# SICRO-Main_v2.net
KiCad netlist of a schematic drawn in EasyEDA Pro
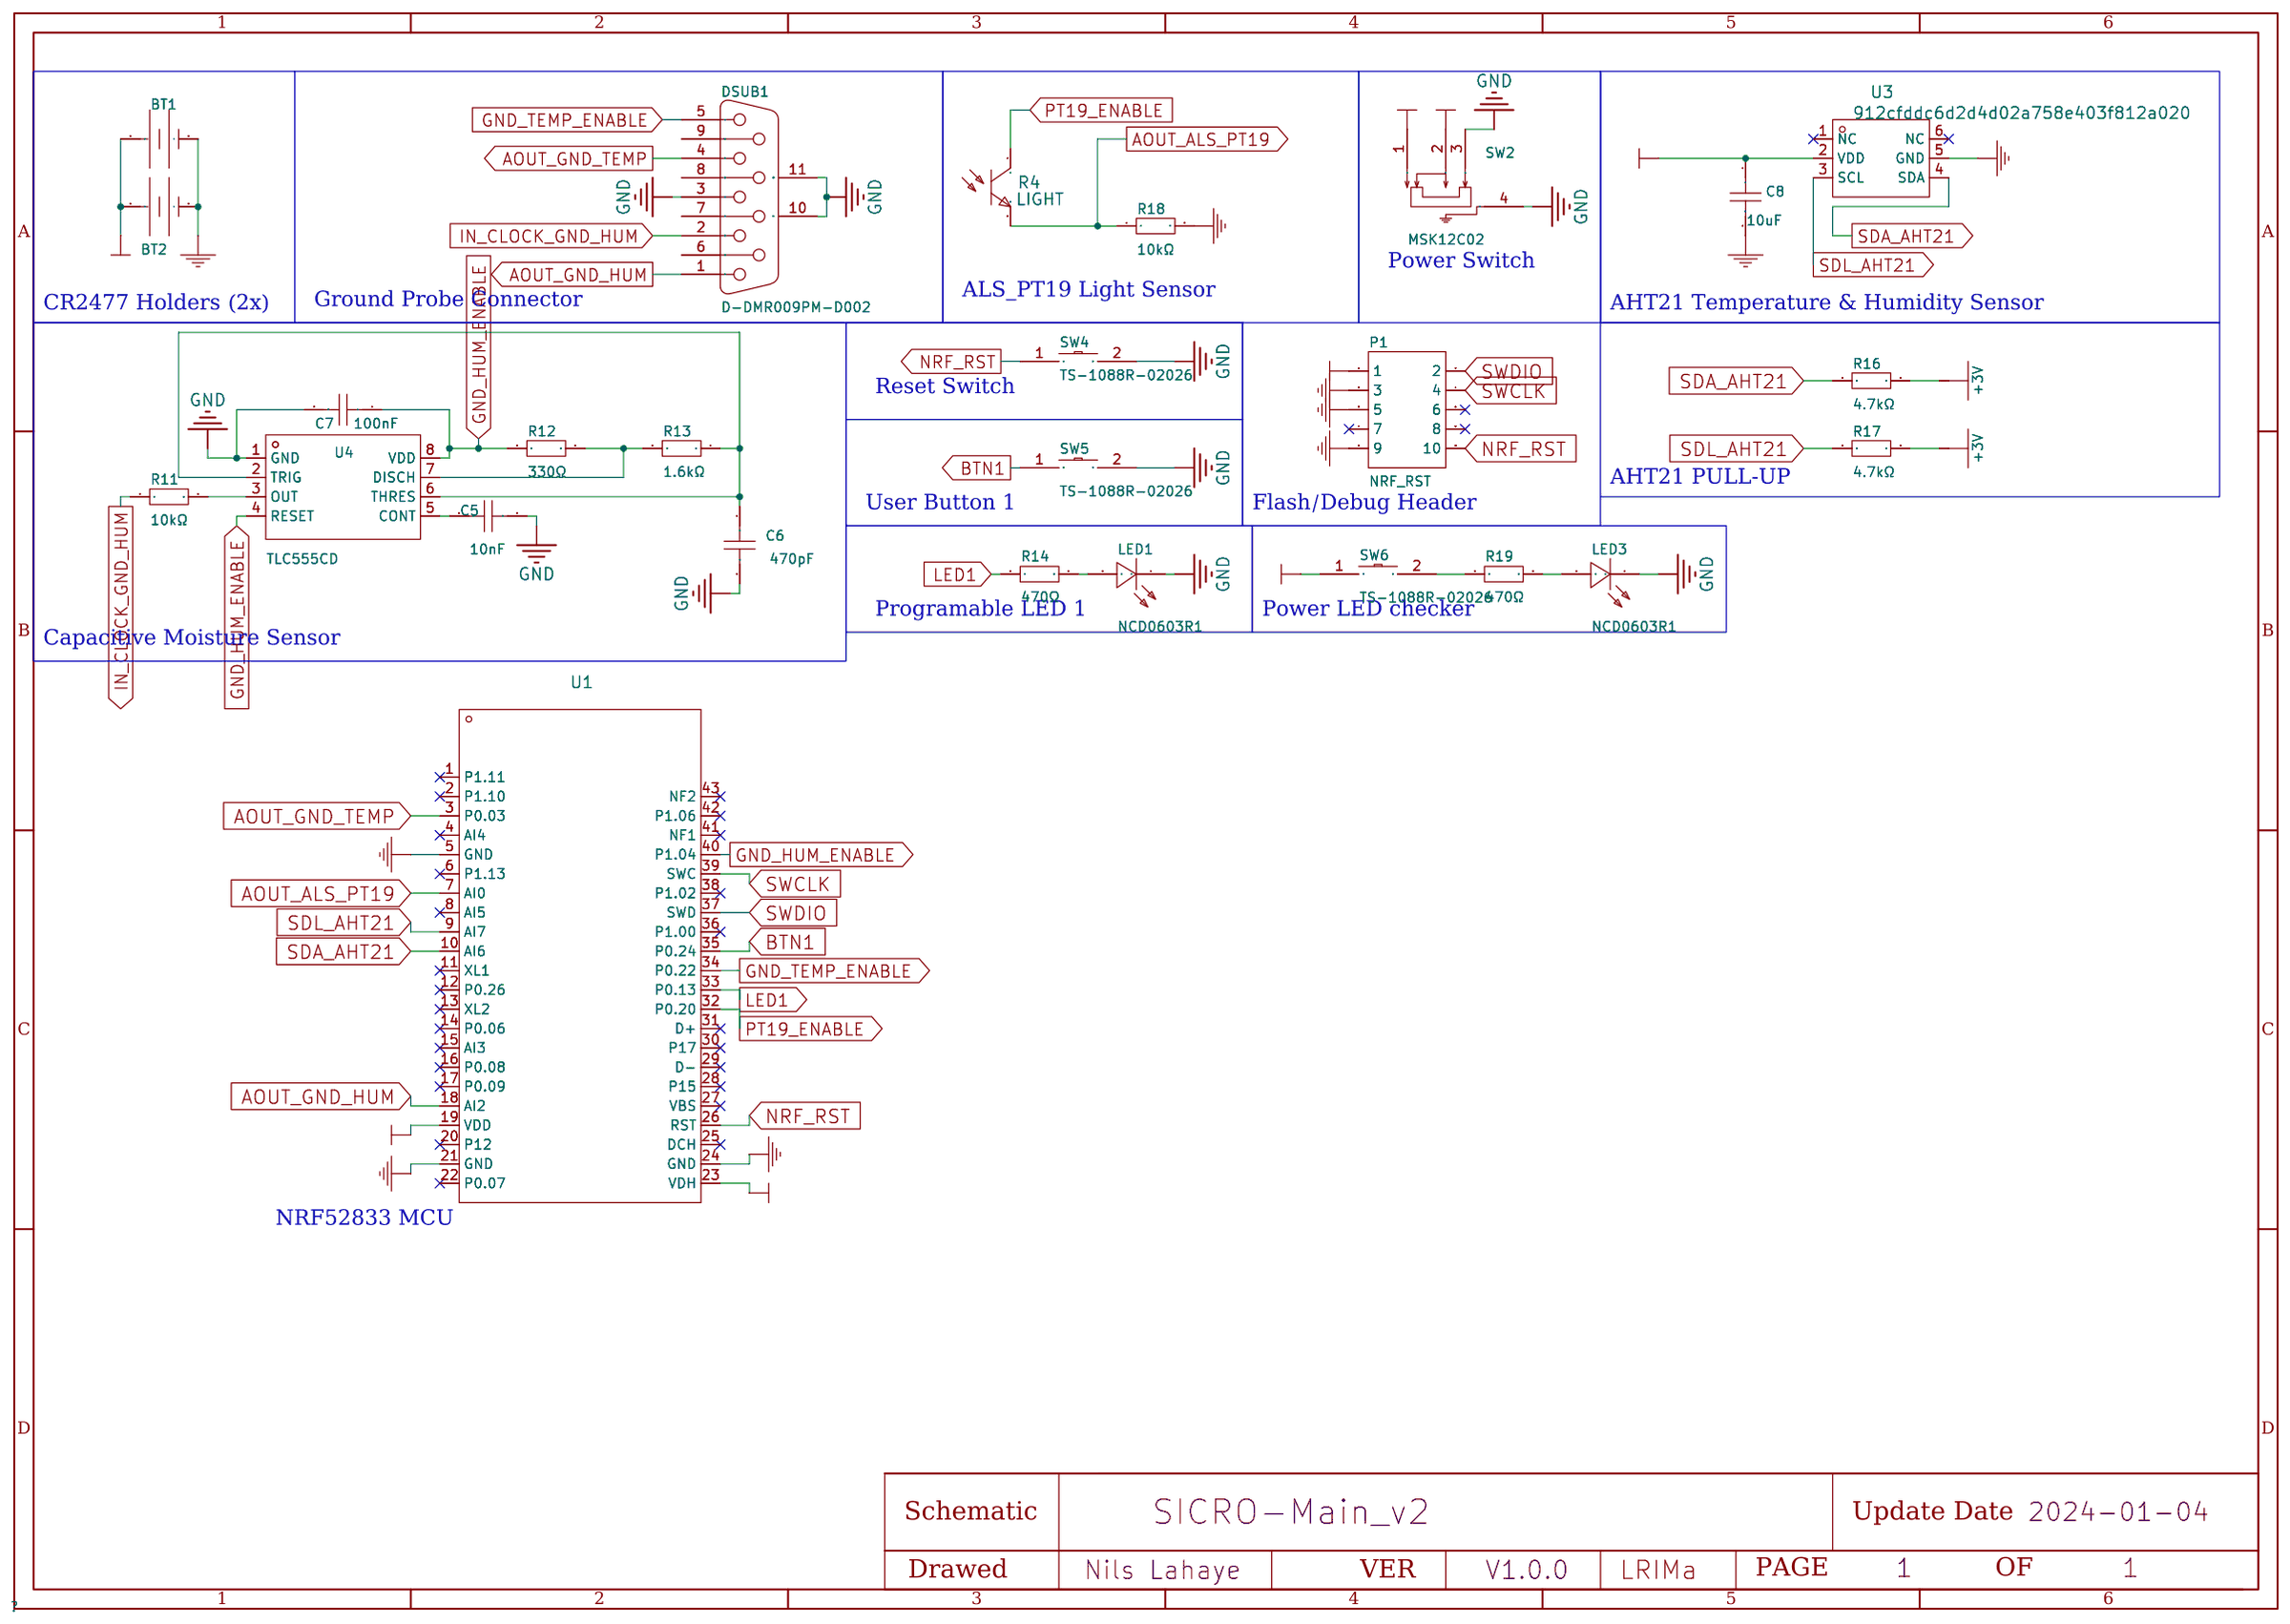
[diagram p0: schematic sheet]

(export (version "E")
  (design (tool "Eeschema 10.0.6"))
  (components
    (comp (ref "BT1")
      (value "BS-24-A1AJ008")
      (footprint "easyedapro:BAT-TH_BS-24-A1AJ013")
      (fields (field (name "Manufacturer") "MYOUNG(美阳)"))
      (libsource (lib "easyedapro") (part "BS-24-A1AJ008"))
    )
    (comp (ref "BT2")
      (value "BS-24-A1AJ008")
      (footprint "easyedapro:BAT-TH_BS-24-A1AJ013")
      (fields (field (name "Manufacturer") "MYOUNG(美阳)"))
      (libsource (lib "easyedapro") (part "BS-24-A1AJ008"))
    )
    (comp (ref "C5")
      (value "10nF")
      (fields
        (field (name "Manufacturer Part") "CC0603KRX7R9BB103")
        (field (name "Manufacturer") "YAGEO(国巨)")
        (field (name "Tolerance") "±10%")
      )
      (libsource (lib "easyedapro") (part "CAP"))
    )
    (comp (ref "C6")
      (value "470pF")
      (fields
        (field (name "Manufacturer Part") "0603B471K500NT")
        (field (name "Manufacturer") "FH(风华)")
        (field (name "Tolerance") "±10%")
      )
      (libsource (lib "easyedapro") (part "CAP"))
    )
    (comp (ref "C7")
      (value "100nF")
      (fields
        (field (name "Manufacturer Part") "0603B104K500NT")
        (field (name "Manufacturer") "FH(风华)")
        (field (name "Tolerance") "±10%")
      )
      (libsource (lib "easyedapro") (part "CAP"))
    )
    (comp (ref "C8")
      (value "10uF")
      (fields
        (field (name "Manufacturer Part") "CL10A106MQ8NNNC")
        (field (name "Manufacturer") "SAMSUNG(三星)")
        (field (name "Tolerance") "±20%")
      )
      (libsource (lib "easyedapro") (part "CAP"))
    )
    (comp (ref "DSUB1")
      (value "D-DMR009PM-D002")
      (footprint "easyedapro:DSUB-TH_DMR-9P")
      (fields (field (name "Manufacturer") "Ckmtw(灿科盟)"))
      (libsource (lib "easyedapro") (part "DMR-9P"))
    )
    (comp (ref "LED1")
      (value "NCD0603R1")
      (description "Emitted Color:红灯")
      (fields (field (name "Manufacturer") "国星光电"))
      (libsource (lib "easyedapro") (part "KT-0603R"))
    )
    (comp (ref "LED3")
      (value "NCD0603R1")
      (description "Emitted Color:红灯")
      (fields (field (name "Manufacturer") "国星光电"))
      (libsource (lib "easyedapro") (part "KT-0603R"))
    )
    (comp (ref "P1")
      (value "NRF_RST")
      (footprint "easyedapro:IDC-TH_10P-P2.54_C5665")
      (fields (field (name "Manufacturer Part") "2.54-2*5P简牛") (field (name "Manufacturer") "BOOMELE(博穆精密)"))
      (libsource (lib "easyedapro") (part "HDR-IDC-2.54-2X5P"))
    )
    (comp (ref "R4")
      (value "LIGHT")
      (footprint "easyedapro:SENSORS-SMD_ALS-PT19")
      (fields
        (field (name "Manufacturer Part") "ALS-PT19-315C/L177/TR8")
        (field (name "Manufacturer") "EVERLIGHT(亿光)")
      )
      (libsource (lib "easyedapro") (part "ALS_PT19"))
    )
    (comp (ref "R11")
      (value "10kΩ")
      (fields
        (field (name "Manufacturer Part") "0603WAF1002T5E")
        (field (name "Manufacturer") "UNI-ROYAL(厚声)")
        (field (name "Tolerance") "±1%")
      )
      (libsource (lib "easyedapro") (part "Res"))
    )
    (comp (ref "R12")
      (value "330Ω")
      (description "Resistance: Tolerance:±1% Tolerance:±1%")
      (fields (field (name "Manufacturer Part") "SCR0603F330R") (field (name "Manufacturer") "VO(翔胜)"))
      (libsource (lib "easyedapro") (part "Res"))
    )
    (comp (ref "R13")
      (value "1.6kΩ")
      (fields
        (field (name "Manufacturer Part") "0603WAF1601T5E")
        (field (name "Manufacturer") "UNI-ROYAL(厚声)")
        (field (name "Tolerance") "±1%")
      )
      (libsource (lib "easyedapro") (part "Res"))
    )
    (comp (ref "R14")
      (value "470Ω")
      (fields
        (field (name "Manufacturer Part") "0603WAF4700T5E")
        (field (name "Manufacturer") "UNI-ROYAL(厚声)")
        (field (name "Tolerance") "±1%")
      )
      (libsource (lib "easyedapro") (part "Res"))
    )
    (comp (ref "R16")
      (value "4.7kΩ")
      (fields
        (field (name "Manufacturer Part") "FRC0603J472 TS")
        (field (name "Manufacturer") "FOJAN(富捷)")
        (field (name "Tolerance") "±5%")
      )
      (libsource (lib "easyedapro") (part "Res"))
    )
    (comp (ref "R17")
      (value "4.7kΩ")
      (fields
        (field (name "Manufacturer Part") "FRC0603J472 TS")
        (field (name "Manufacturer") "FOJAN(富捷)")
        (field (name "Tolerance") "±5%")
      )
      (libsource (lib "easyedapro") (part "Res"))
    )
    (comp (ref "R18")
      (value "10kΩ")
      (fields
        (field (name "Manufacturer Part") "0603WAF1002T5E")
        (field (name "Manufacturer") "UNI-ROYAL(厚声)")
        (field (name "Tolerance") "±1%")
      )
      (libsource (lib "easyedapro") (part "Res"))
    )
    (comp (ref "R19")
      (value "470Ω")
      (fields
        (field (name "Manufacturer Part") "0603WAF4700T5E")
        (field (name "Manufacturer") "UNI-ROYAL(厚声)")
        (field (name "Tolerance") "±1%")
      )
      (libsource (lib "easyedapro") (part "Res"))
    )
    (comp (ref "SW2")
      (value "MSK12C02")
      (fields (field (name "Manufacturer") "SHOU HAN(首韩)"))
      (libsource (lib "easyedapro") (part "MSK12C02-HB"))
    )
    (comp (ref "SW4")
      (value "TS-1088R-02026")
      (fields (field (name "Manufacturer") "XUNPU(讯普)"))
      (libsource (lib "easyedapro") (part "TS-1101-C-W"))
    )
    (comp (ref "SW5")
      (value "TS-1088R-02026")
      (fields (field (name "Manufacturer") "XUNPU(讯普)"))
      (libsource (lib "easyedapro") (part "TS-1101-C-W"))
    )
    (comp (ref "SW6")
      (value "TS-1088R-02026")
      (fields (field (name "Manufacturer") "XUNPU(讯普)"))
      (libsource (lib "easyedapro") (part "TS-1101-C-W"))
    )
    (comp (ref "U1")
      (value "NRF_RST")
      (footprint "easyedapro:SMD-43_L18.0-W13.0-P1.27-E73-2G4M08S1E")
      (fields (field (name "Manufacturer Part") "E73-2G4M08S1E"))
      (libsource (lib "easyedapro") (part "E73-2G4M08S1E"))
    )
    (comp (ref "U3")
      (value "912cfddc6d2d4d02a758e403f812a020")
      (footprint "easyedapro:SENSOR-SMD_L3.0-W3.0-P1.00-BR")
      (fields (field (name "Manufacturer Part") "AHT21") (field (name "Manufacturer") "广州奥松"))
      (libsource (lib "easyedapro") (part "AHT21"))
    )
    (comp (ref "U4")
      (value "TLC555CD")
      (footprint "easyedapro:SOIC-8_L4.9-W3.9-P1.27-LS6.0-BL")
      (fields (field (name "Manufacturer") "TI(德州仪器)"))
      (libsource (lib "easyedapro") (part "TLC555CD"))
    )
  )
  (nets
    (net (code "1") (name "+3V") (class "Default")
      (node (ref "C8") (pin "1") (pinfunction "1_1") (pintype "input"))
      (node (ref "P1") (pin "1") (pinfunction "1_1") (pintype "input"))
      (node (ref "R16") (pin "2") (pinfunction "2_2") (pintype "input"))
      (node (ref "R17") (pin "2") (pinfunction "2_2") (pintype "input"))
      (node (ref "SW2") (pin "2") (pinfunction "2_2") (pintype "input"))
      (node (ref "SW6") (pin "1") (pinfunction "1_1") (pintype "unspecified"))
      (node (ref "U1") (pin "19") (pinfunction "VDD_19") (pintype "input"))
      (node (ref "U1") (pin "23") (pinfunction "VDH_23") (pintype "input"))
      (node (ref "U3") (pin "2") (pinfunction "VDD_2") (pintype "input"))
    )
    (net (code "2") (name "+3V_S") (class "Default")
      (node (ref "BT1") (pin "1") (pinfunction "+_1") (pintype "input"))
      (node (ref "BT2") (pin "1") (pinfunction "+_1") (pintype "input"))
      (node (ref "SW2") (pin "1") (pinfunction "1_1") (pintype "input"))
    )
    (net (code "3") (name "AOUT_ALS_PT19") (class "Default")
      (node (ref "R18") (pin "1") (pinfunction "1_1") (pintype "input"))
      (node (ref "R4") (pin "2") (pinfunction "2_2") (pintype "input"))
      (node (ref "U1") (pin "7") (pinfunction "AI0_7") (pintype "input"))
    )
    (net (code "4") (name "AOUT_GND_HUM") (class "Default")
      (node (ref "DSUB1") (pin "1") (pinfunction "1_1") (pintype "input"))
      (node (ref "U1") (pin "18") (pinfunction "AI2_18") (pintype "input"))
    )
    (net (code "5") (name "AOUT_GND_TEMP") (class "Default")
      (node (ref "DSUB1") (pin "4") (pinfunction "4_4") (pintype "input"))
      (node (ref "U1") (pin "3") (pinfunction "P0.03_3") (pintype "input"))
    )
    (net (code "6") (name "BTN1") (class "Default")
      (node (ref "SW5") (pin "1") (pinfunction "1_1") (pintype "unspecified"))
      (node (ref "U1") (pin "35") (pinfunction "P0.24_35") (pintype "input"))
    )
    (net (code "7") (name "GND") (class "Default")
      (node (ref "BT1") (pin "2") (pinfunction "-_2") (pintype "input"))
      (node (ref "BT2") (pin "2") (pinfunction "-_2") (pintype "input"))
      (node (ref "C5") (pin "1") (pinfunction "1_1") (pintype "input"))
      (node (ref "C6") (pin "2") (pinfunction "2_2") (pintype "input"))
      (node (ref "C7") (pin "2") (pinfunction "2_2") (pintype "input"))
      (node (ref "C8") (pin "2") (pinfunction "2_2") (pintype "input"))
      (node (ref "DSUB1") (pin "10") (pinfunction "MH1_10") (pintype "input"))
      (node (ref "DSUB1") (pin "11") (pinfunction "MH2_11") (pintype "input"))
      (node (ref "DSUB1") (pin "3") (pinfunction "3_3") (pintype "input"))
      (node (ref "LED1") (pin "1") (pinfunction "K_1") (pintype "input"))
      (node (ref "LED3") (pin "1") (pinfunction "K_1") (pintype "input"))
      (node (ref "P1") (pin "3") (pinfunction "3_3") (pintype "input"))
      (node (ref "P1") (pin "5") (pinfunction "5_5") (pintype "input"))
      (node (ref "P1") (pin "9") (pinfunction "9_9") (pintype "input"))
      (node (ref "R18") (pin "2") (pinfunction "2_2") (pintype "input"))
      (node (ref "SW2") (pin "3") (pinfunction "3_3") (pintype "input"))
      (node (ref "SW2") (pin "4") (pinfunction "4_4") (pintype "input"))
      (node (ref "SW4") (pin "2") (pinfunction "2_2") (pintype "unspecified"))
      (node (ref "SW5") (pin "2") (pinfunction "2_2") (pintype "unspecified"))
      (node (ref "U1") (pin "21") (pinfunction "GND_21") (pintype "input"))
      (node (ref "U1") (pin "24") (pinfunction "GND_24") (pintype "input"))
      (node (ref "U1") (pin "5") (pinfunction "GND_5") (pintype "input"))
      (node (ref "U3") (pin "5") (pinfunction "GND_5") (pintype "input"))
      (node (ref "U4") (pin "1") (pinfunction "GND_1") (pintype "input"))
    )
    (net (code "8") (name "GND_HUM_ENABLE") (class "Default")
      (node (ref "C7") (pin "1") (pinfunction "1_1") (pintype "input"))
      (node (ref "R12") (pin "2") (pinfunction "2_2") (pintype "input"))
      (node (ref "U1") (pin "40") (pinfunction "P1.04_40") (pintype "input"))
      (node (ref "U4") (pin "4") (pinfunction "RESET_4") (pintype "input"))
      (node (ref "U4") (pin "8") (pinfunction "VDD_8") (pintype "input"))
    )
    (net (code "9") (name "GND_TEMP_ENABLE") (class "Default")
      (node (ref "DSUB1") (pin "5") (pinfunction "5_5") (pintype "input"))
      (node (ref "U1") (pin "34") (pinfunction "P0.22_34") (pintype "input"))
    )
    (net (code "10") (name "IN_CLOCK_GND_HUM") (class "Default")
      (node (ref "DSUB1") (pin "2") (pinfunction "2_2") (pintype "input"))
      (node (ref "R11") (pin "1") (pinfunction "1_1") (pintype "input"))
    )
    (net (code "11") (name "LED1") (class "Default")
      (node (ref "R14") (pin "1") (pinfunction "1_1") (pintype "input"))
      (node (ref "U1") (pin "33") (pinfunction "P0.13_33") (pintype "input"))
    )
    (net (code "12") (name "NRF_RST") (class "Default")
      (node (ref "P1") (pin "10") (pinfunction "10_10") (pintype "input"))
      (node (ref "SW4") (pin "1") (pinfunction "1_1") (pintype "unspecified"))
      (node (ref "U1") (pin "26") (pinfunction "RST_26") (pintype "input"))
    )
    (net (code "13") (name "Net-(LED1-A)") (class "Default")
      (node (ref "LED1") (pin "2") (pinfunction "A_2") (pintype "input"))
      (node (ref "R14") (pin "2") (pinfunction "2_2") (pintype "input"))
    )
    (net (code "14") (name "Net-(LED3-A)") (class "Default")
      (node (ref "LED3") (pin "2") (pinfunction "A_2") (pintype "input"))
      (node (ref "R19") (pin "2") (pinfunction "2_2") (pintype "input"))
    )
    (net (code "15") (name "Net-(R19-Pad1)") (class "Default")
      (node (ref "R19") (pin "1") (pinfunction "1_1") (pintype "input"))
      (node (ref "SW6") (pin "2") (pinfunction "2_2") (pintype "unspecified"))
    )
    (net (code "16") (name "Net-(U4-CONT)") (class "Default")
      (node (ref "C5") (pin "2") (pinfunction "2_2") (pintype "input"))
      (node (ref "U4") (pin "5") (pinfunction "CONT_5") (pintype "input"))
    )
    (net (code "17") (name "Net-(U4-DISCH)") (class "Default")
      (node (ref "R12") (pin "1") (pinfunction "1_1") (pintype "input"))
      (node (ref "R13") (pin "2") (pinfunction "2_2") (pintype "input"))
      (node (ref "U4") (pin "7") (pinfunction "DISCH_7") (pintype "input"))
    )
    (net (code "18") (name "Net-(U4-OUT)") (class "Default")
      (node (ref "R11") (pin "2") (pinfunction "2_2") (pintype "input"))
      (node (ref "U4") (pin "3") (pinfunction "OUT_3") (pintype "input"))
    )
    (net (code "19") (name "Net-(U4-THRES)") (class "Default")
      (node (ref "C6") (pin "1") (pinfunction "1_1") (pintype "input"))
      (node (ref "R13") (pin "1") (pinfunction "1_1") (pintype "input"))
      (node (ref "U4") (pin "2") (pinfunction "TRIG_2") (pintype "input"))
      (node (ref "U4") (pin "6") (pinfunction "THRES_6") (pintype "input"))
    )
    (net (code "20") (name "PT19_ENABLE") (class "Default")
      (node (ref "R4") (pin "1") (pinfunction "1_1") (pintype "input"))
      (node (ref "U1") (pin "32") (pinfunction "P0.20_32") (pintype "input"))
    )
    (net (code "21") (name "SDA_AHT21") (class "Default")
      (node (ref "R16") (pin "1") (pinfunction "1_1") (pintype "input"))
      (node (ref "U1") (pin "10") (pinfunction "AI6_10") (pintype "input"))
      (node (ref "U3") (pin "4") (pinfunction "SDA_4") (pintype "input"))
    )
    (net (code "22") (name "SDL_AHT21") (class "Default")
      (node (ref "R17") (pin "1") (pinfunction "1_1") (pintype "input"))
      (node (ref "U1") (pin "9") (pinfunction "AI7_9") (pintype "input"))
      (node (ref "U3") (pin "3") (pinfunction "SCL_3") (pintype "input"))
    )
    (net (code "23") (name "SWCLK") (class "Default")
      (node (ref "P1") (pin "4") (pinfunction "4_4") (pintype "input"))
      (node (ref "U1") (pin "39") (pinfunction "SWC_39") (pintype "input"))
    )
    (net (code "24") (name "SWDIO") (class "Default")
      (node (ref "P1") (pin "2") (pinfunction "2_2") (pintype "input"))
      (node (ref "U1") (pin "37") (pinfunction "SWD_37") (pintype "input"))
    )
    (net (code "25") (name "unconnected-(DSUB1-Pad6)") (class "Default")
      (node (ref "DSUB1") (pin "6") (pinfunction "6_6") (pintype "input"))
    )
    (net (code "26") (name "unconnected-(DSUB1-Pad7)") (class "Default")
      (node (ref "DSUB1") (pin "7") (pinfunction "7_7") (pintype "input"))
    )
    (net (code "27") (name "unconnected-(DSUB1-Pad8)") (class "Default")
      (node (ref "DSUB1") (pin "8") (pinfunction "8_8") (pintype "input"))
    )
    (net (code "28") (name "unconnected-(DSUB1-Pad9)") (class "Default")
      (node (ref "DSUB1") (pin "9") (pinfunction "9_9") (pintype "input"))
    )
    (net (code "29") (name "unconnected-(P1-Pad6)") (class "Default")
      (node (ref "P1") (pin "6") (pinfunction "6_6") (pintype "input+no_connect"))
    )
    (net (code "30") (name "unconnected-(P1-Pad7)") (class "Default")
      (node (ref "P1") (pin "7") (pinfunction "7_7") (pintype "input+no_connect"))
    )
    (net (code "31") (name "unconnected-(P1-Pad8)") (class "Default")
      (node (ref "P1") (pin "8") (pinfunction "8_8") (pintype "input+no_connect"))
    )
    (net (code "32") (name "unconnected-(U1-AI3-Pad15)") (class "Default")
      (node (ref "U1") (pin "15") (pinfunction "AI3_15") (pintype "input+no_connect"))
    )
    (net (code "33") (name "unconnected-(U1-AI4-Pad4)") (class "Default")
      (node (ref "U1") (pin "4") (pinfunction "AI4_4") (pintype "input+no_connect"))
    )
    (net (code "34") (name "unconnected-(U1-AI5-Pad8)") (class "Default")
      (node (ref "U1") (pin "8") (pinfunction "AI5_8") (pintype "input+no_connect"))
    )
    (net (code "35") (name "unconnected-(U1-D+-Pad31)") (class "Default")
      (node (ref "U1") (pin "31") (pinfunction "D+_31") (pintype "input+no_connect"))
    )
    (net (code "36") (name "unconnected-(U1-D--Pad29)") (class "Default")
      (node (ref "U1") (pin "29") (pinfunction "D-_29") (pintype "input+no_connect"))
    )
    (net (code "37") (name "unconnected-(U1-DCH-Pad25)") (class "Default")
      (node (ref "U1") (pin "25") (pinfunction "DCH_25") (pintype "input+no_connect"))
    )
    (net (code "38") (name "unconnected-(U1-NF1-Pad41)") (class "Default")
      (node (ref "U1") (pin "41") (pinfunction "NF1_41") (pintype "input+no_connect"))
    )
    (net (code "39") (name "unconnected-(U1-NF2-Pad43)") (class "Default")
      (node (ref "U1") (pin "43") (pinfunction "NF2_43") (pintype "input+no_connect"))
    )
    (net (code "40") (name "unconnected-(U1-P0.06-Pad14)") (class "Default")
      (node (ref "U1") (pin "14") (pinfunction "P0.06_14") (pintype "input+no_connect"))
    )
    (net (code "41") (name "unconnected-(U1-P0.07-Pad22)") (class "Default")
      (node (ref "U1") (pin "22") (pinfunction "P0.07_22") (pintype "input+no_connect"))
    )
    (net (code "42") (name "unconnected-(U1-P0.08-Pad16)") (class "Default")
      (node (ref "U1") (pin "16") (pinfunction "P0.08_16") (pintype "input+no_connect"))
    )
    (net (code "43") (name "unconnected-(U1-P0.09-Pad17)") (class "Default")
      (node (ref "U1") (pin "17") (pinfunction "P0.09_17") (pintype "input+no_connect"))
    )
    (net (code "44") (name "unconnected-(U1-P0.26-Pad12)") (class "Default")
      (node (ref "U1") (pin "12") (pinfunction "P0.26_12") (pintype "input+no_connect"))
    )
    (net (code "45") (name "unconnected-(U1-P1.00-Pad36)") (class "Default")
      (node (ref "U1") (pin "36") (pinfunction "P1.00_36") (pintype "input+no_connect"))
    )
    (net (code "46") (name "unconnected-(U1-P1.02-Pad38)") (class "Default")
      (node (ref "U1") (pin "38") (pinfunction "P1.02_38") (pintype "input+no_connect"))
    )
    (net (code "47") (name "unconnected-(U1-P1.06-Pad42)") (class "Default")
      (node (ref "U1") (pin "42") (pinfunction "P1.06_42") (pintype "input+no_connect"))
    )
    (net (code "48") (name "unconnected-(U1-P1.10-Pad2)") (class "Default")
      (node (ref "U1") (pin "2") (pinfunction "P1.10_2") (pintype "input+no_connect"))
    )
    (net (code "49") (name "unconnected-(U1-P1.11-Pad1)") (class "Default")
      (node (ref "U1") (pin "1") (pinfunction "P1.11_1") (pintype "input+no_connect"))
    )
    (net (code "50") (name "unconnected-(U1-P1.13-Pad6)") (class "Default")
      (node (ref "U1") (pin "6") (pinfunction "P1.13_6") (pintype "input+no_connect"))
    )
    (net (code "51") (name "unconnected-(U1-P12-Pad20)") (class "Default")
      (node (ref "U1") (pin "20") (pinfunction "P12_20") (pintype "input+no_connect"))
    )
    (net (code "52") (name "unconnected-(U1-P15-Pad28)") (class "Default")
      (node (ref "U1") (pin "28") (pinfunction "P15_28") (pintype "input+no_connect"))
    )
    (net (code "53") (name "unconnected-(U1-P17-Pad30)") (class "Default")
      (node (ref "U1") (pin "30") (pinfunction "P17_30") (pintype "input+no_connect"))
    )
    (net (code "54") (name "unconnected-(U1-VBS-Pad27)") (class "Default")
      (node (ref "U1") (pin "27") (pinfunction "VBS_27") (pintype "input+no_connect"))
    )
    (net (code "55") (name "unconnected-(U1-XL1-Pad11)") (class "Default")
      (node (ref "U1") (pin "11") (pinfunction "XL1_11") (pintype "input+no_connect"))
    )
    (net (code "56") (name "unconnected-(U1-XL2-Pad13)") (class "Default")
      (node (ref "U1") (pin "13") (pinfunction "XL2_13") (pintype "input+no_connect"))
    )
    (net (code "57") (name "unconnected-(U3-NC-Pad1)") (class "Default")
      (node (ref "U3") (pin "1") (pinfunction "NC_1") (pintype "input+no_connect"))
    )
    (net (code "58") (name "unconnected-(U3-NC-Pad6)") (class "Default")
      (node (ref "U3") (pin "6") (pinfunction "NC_6") (pintype "input+no_connect"))
    )
  )
)
